# GD_AirIrDA_Top.net
KiCad netlist of a schematic drawn in Altium Designer
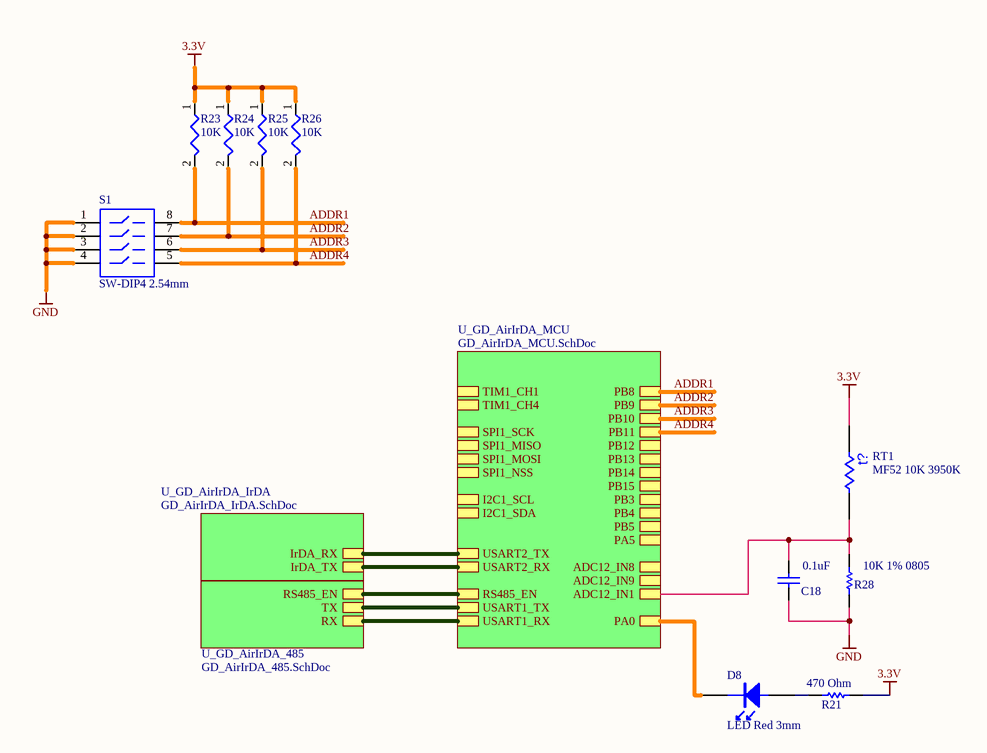
[diagram p0: GD_AirIrDA_Top.SchDoc]

(export (version "E")
  (design (tool "Eeschema 10.0.6"))
  (components
    (comp (ref "C18")
      (value "0.1uF")
      (footprint "CAPC0805(2012)100_N")
      (description "CAP 0.1uF 50V ±20% 0805 (2012 Metric) Thickness 1mm SMD")
      (fields (field (name "TOLERANCE") "20%") (field (name "Comment") "CAP 0.1uF 20% 50V 0805"))
      (libsource (lib "Altium Content Vault") (part "CMP-1036-00070-1"))
    )
    (comp (ref "D8") (value "LED Red 3mm") (footprint "LED_DIP") (libsource (lib "*") (part "LED")))
    (comp (ref "R21")
      (value "470 Ohm")
      (footprint "RESC0805(2012)_L")
      (description "470Ohm 0.125W 5% 0805 (2012 Metric)  SMD")
      (fields (field (name "POWER") "0.125 W") (field (name "TOLERANCE") "5 %"))
      (libsource (lib "Altium Content Vault") (part "CMP-1013-00098-1"))
    )
    (comp (ref "R23")
      (value "10K")
      (footprint "R0805")
      (description "RES THICK_FILM SMD 10K ohm 5% 1/10W ROHS 0603")
      (fields (field (name "MANUFACTURER") "YAGEO") (field (name "Comment") "10K 5% 0805"))
      (libsource (lib "enlogic") (part "RES"))
    )
    (comp (ref "R24")
      (value "10K")
      (footprint "R0805")
      (description "RES THICK_FILM SMD 10K ohm 5% 1/10W ROHS 0603")
      (fields (field (name "MANUFACTURER") "YAGEO") (field (name "Comment") "10K 5% 0805"))
      (libsource (lib "enlogic") (part "RES"))
    )
    (comp (ref "R25")
      (value "10K")
      (footprint "R0805")
      (description "RES THICK_FILM SMD 10K ohm 5% 1/10W ROHS 0603")
      (fields (field (name "MANUFACTURER") "YAGEO") (field (name "Comment") "10K 5% 0805"))
      (libsource (lib "enlogic") (part "RES"))
    )
    (comp (ref "R26")
      (value "10K")
      (footprint "R0805")
      (description "RES THICK_FILM SMD 10K ohm 5% 1/10W ROHS 0603")
      (fields (field (name "MANUFACTURER") "YAGEO") (field (name "Comment") "10K 5% 0805"))
      (libsource (lib "enlogic") (part "RES"))
    )
    (comp (ref "R28")
      (value "10K 1% 0805")
      (footprint "RESC0805(2012)_L")
      (description "10K 0.125W 5% 0805 (2012 Metric)  SMD")
      (fields (field (name "POWER") "0.125 W") (field (name "TOLERANCE") "1 %"))
      (libsource (lib "Altium Content Vault") (part "CMP-1013-00098-1"))
    )
    (comp (ref "RT1")
      (value "MF52 10K 3950K")
      (footprint "NTC-MF52")
      (description "Thermistor")
      (fields (field (name "PUBLISHER") "Altium Limited"))
      (libsource (lib "Miscellaneous Devices") (part "Res Thermal"))
    )
    (comp (ref "S1")
      (value "SW-DIP4 2.54mm")
      (footprint "SW_4P")
      (description "侧拨 4位")
      (fields (field (name "MANUFACTURER") "WE") (field (name "PUBLISHER") "Altium Limited"))
      (libsource (lib "Miscellaneous Devices") (part "SW-DIP4"))
    )
  )
  (nets
    (net (code "1") (name "/ADC12_IN1") (class "Default")
      (node (ref "C18") (pin "2") (pinfunction "2_2") (pintype "passive"))
      (node (ref "R28") (pin "1") (pinfunction "1_1") (pintype "passive"))
      (node (ref "RT1") (pin "2") (pinfunction "2_2") (pintype "passive"))
    )
    (net (code "4") (name "/ADDR1") (class "Default")
      (node (ref "R23") (pin "2") (pinfunction "2_2") (pintype "passive"))
      (node (ref "S1") (pin "8") (pinfunction "8_8") (pintype "passive"))
    )
    (net (code "5") (name "/ADDR2") (class "Default")
      (node (ref "R24") (pin "2") (pinfunction "2_2") (pintype "passive"))
      (node (ref "S1") (pin "7") (pinfunction "7_7") (pintype "passive"))
    )
    (net (code "6") (name "/ADDR3") (class "Default")
      (node (ref "R25") (pin "2") (pinfunction "2_2") (pintype "passive"))
      (node (ref "S1") (pin "6") (pinfunction "6_6") (pintype "passive"))
    )
    (net (code "7") (name "/ADDR4") (class "Default")
      (node (ref "R26") (pin "2") (pinfunction "2_2") (pintype "passive"))
      (node (ref "S1") (pin "5") (pinfunction "5_5") (pintype "passive"))
    )
    (net (code "12") (name "/PA0") (class "Default")
      (node (ref "D8") (pin "2") (pinfunction "2_2") (pintype "passive"))
    )
    (net (code "30") (name "3.3V") (class "Default")
      (node (ref "R21") (pin "2") (pinfunction "2_2") (pintype "passive"))
      (node (ref "R23") (pin "1") (pinfunction "1_1") (pintype "passive"))
      (node (ref "R24") (pin "1") (pinfunction "1_1") (pintype "passive"))
      (node (ref "R25") (pin "1") (pinfunction "1_1") (pintype "passive"))
      (node (ref "R26") (pin "1") (pinfunction "1_1") (pintype "passive"))
      (node (ref "RT1") (pin "1") (pinfunction "1_1") (pintype "passive"))
    )
    (net (code "31") (name "GND") (class "Default")
      (node (ref "C18") (pin "1") (pinfunction "1_1") (pintype "passive"))
      (node (ref "R28") (pin "2") (pinfunction "2_2") (pintype "passive"))
      (node (ref "S1") (pin "1") (pinfunction "1_1") (pintype "passive"))
      (node (ref "S1") (pin "2") (pinfunction "2_2") (pintype "passive"))
      (node (ref "S1") (pin "3") (pinfunction "3_3") (pintype "passive"))
      (node (ref "S1") (pin "4") (pinfunction "4_4") (pintype "passive"))
    )
    (net (code "32") (name "Net-(D8-Pad1)") (class "Default")
      (node (ref "D8") (pin "1") (pinfunction "1_1") (pintype "passive"))
      (node (ref "R21") (pin "1") (pinfunction "1_1") (pintype "passive"))
    )
  )
)
